# Task1.net
KiCad netlist of a schematic drawn in Altium Designer
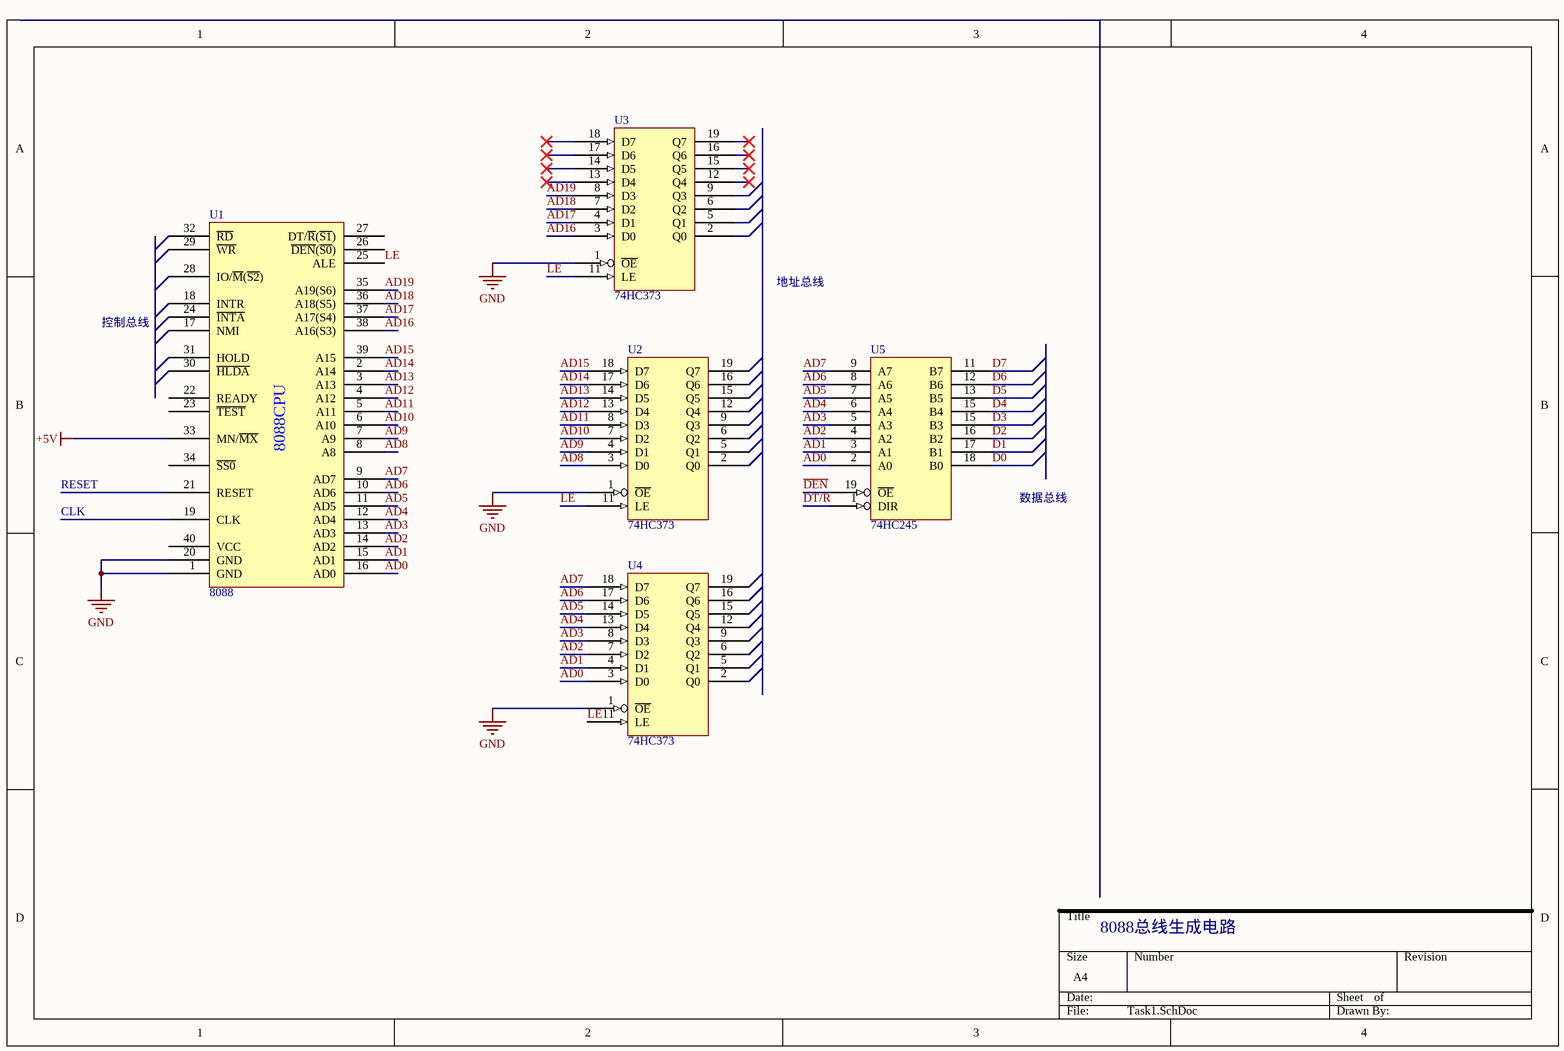
[diagram p0: Task1.SchDoc]

(export (version "E")
  (design (tool "Eeschema 10.0.6"))
  (components
    (comp (ref "U1") (value "8088") (libsource (lib "8088ThreeBuses") (part "8088")))
    (comp (ref "U2") (value "74HC373") (libsource (lib "8088ThreeBuses") (part "74HC373")))
    (comp (ref "U3") (value "74HC373") (libsource (lib "8088ThreeBuses") (part "74HC373")))
    (comp (ref "U4") (value "74HC373") (libsource (lib "8088ThreeBuses") (part "74HC373")))
    (comp (ref "U5") (value "74HC245") (libsource (lib "8088ThreeBuses") (part "74HC245")))
  )
  (nets
    (net (code "1") (name "+5V") (class "Default")
      (node (ref "U1") (pin "33") (pinfunction "MN/~{MX}_33") (pintype "passive"))
    )
    (net (code "2") (name "/AD0") (class "Default")
      (node (ref "U1") (pin "16") (pinfunction "AD0_16") (pintype "passive"))
      (node (ref "U4") (pin "3") (pinfunction "D0_3") (pintype "input"))
      (node (ref "U5") (pin "2") (pinfunction "A0_2") (pintype "passive"))
    )
    (net (code "3") (name "/AD1") (class "Default")
      (node (ref "U1") (pin "15") (pinfunction "AD1_15") (pintype "passive"))
      (node (ref "U4") (pin "4") (pinfunction "D1_4") (pintype "input"))
      (node (ref "U5") (pin "3") (pinfunction "A1_3") (pintype "passive"))
    )
    (net (code "4") (name "/AD2") (class "Default")
      (node (ref "U1") (pin "14") (pinfunction "AD2_14") (pintype "passive"))
      (node (ref "U4") (pin "7") (pinfunction "D2_7") (pintype "input"))
      (node (ref "U5") (pin "4") (pinfunction "A2_4") (pintype "passive"))
    )
    (net (code "5") (name "/AD3") (class "Default")
      (node (ref "U1") (pin "13") (pinfunction "AD3_13") (pintype "passive"))
      (node (ref "U4") (pin "8") (pinfunction "D3_8") (pintype "input"))
      (node (ref "U5") (pin "5") (pinfunction "A3_5") (pintype "passive"))
    )
    (net (code "6") (name "/AD4") (class "Default")
      (node (ref "U1") (pin "12") (pinfunction "AD4_12") (pintype "passive"))
      (node (ref "U4") (pin "13") (pinfunction "D4_13") (pintype "input"))
      (node (ref "U5") (pin "6") (pinfunction "A4_6") (pintype "passive"))
    )
    (net (code "7") (name "/AD5") (class "Default")
      (node (ref "U1") (pin "11") (pinfunction "AD5_11") (pintype "passive"))
      (node (ref "U4") (pin "14") (pinfunction "D5_14") (pintype "input"))
      (node (ref "U5") (pin "7") (pinfunction "A5_7") (pintype "passive"))
    )
    (net (code "8") (name "/AD6") (class "Default")
      (node (ref "U1") (pin "10") (pinfunction "AD6_10") (pintype "passive"))
      (node (ref "U4") (pin "17") (pinfunction "D6_17") (pintype "input"))
      (node (ref "U5") (pin "8") (pinfunction "A6_8") (pintype "passive"))
    )
    (net (code "9") (name "/AD7") (class "Default")
      (node (ref "U1") (pin "9") (pinfunction "AD7_9") (pintype "passive"))
      (node (ref "U4") (pin "18") (pinfunction "D7_18") (pintype "input"))
      (node (ref "U5") (pin "9") (pinfunction "A7_9") (pintype "passive"))
    )
    (net (code "10") (name "/AD8") (class "Default")
      (node (ref "U1") (pin "8") (pinfunction "A8_8") (pintype "passive"))
      (node (ref "U2") (pin "3") (pinfunction "D0_3") (pintype "input"))
    )
    (net (code "11") (name "/AD9") (class "Default")
      (node (ref "U1") (pin "7") (pinfunction "A9_7") (pintype "passive"))
      (node (ref "U2") (pin "4") (pinfunction "D1_4") (pintype "input"))
    )
    (net (code "12") (name "/AD10") (class "Default")
      (node (ref "U1") (pin "6") (pinfunction "A10_6") (pintype "passive"))
      (node (ref "U2") (pin "7") (pinfunction "D2_7") (pintype "input"))
    )
    (net (code "13") (name "/AD11") (class "Default")
      (node (ref "U1") (pin "5") (pinfunction "A11_5") (pintype "passive"))
      (node (ref "U2") (pin "8") (pinfunction "D3_8") (pintype "input"))
    )
    (net (code "14") (name "/AD12") (class "Default")
      (node (ref "U1") (pin "4") (pinfunction "A12_4") (pintype "passive"))
      (node (ref "U2") (pin "13") (pinfunction "D4_13") (pintype "input"))
    )
    (net (code "15") (name "/AD13") (class "Default")
      (node (ref "U1") (pin "3") (pinfunction "A13_3") (pintype "passive"))
      (node (ref "U2") (pin "14") (pinfunction "D5_14") (pintype "input"))
    )
    (net (code "16") (name "/AD14") (class "Default")
      (node (ref "U1") (pin "2") (pinfunction "A14_2") (pintype "passive"))
      (node (ref "U2") (pin "17") (pinfunction "D6_17") (pintype "input"))
    )
    (net (code "17") (name "/AD15") (class "Default")
      (node (ref "U1") (pin "39") (pinfunction "A15_39") (pintype "passive"))
      (node (ref "U2") (pin "18") (pinfunction "D7_18") (pintype "input"))
    )
    (net (code "18") (name "/AD16") (class "Default")
      (node (ref "U1") (pin "38") (pinfunction "A16(S3)_38") (pintype "passive"))
      (node (ref "U3") (pin "3") (pinfunction "D0_3") (pintype "input"))
    )
    (net (code "19") (name "/AD17") (class "Default")
      (node (ref "U1") (pin "37") (pinfunction "A17(S4)_37") (pintype "passive"))
      (node (ref "U3") (pin "4") (pinfunction "D1_4") (pintype "input"))
    )
    (net (code "20") (name "/AD18") (class "Default")
      (node (ref "U1") (pin "36") (pinfunction "A18(S5)_36") (pintype "passive"))
      (node (ref "U3") (pin "7") (pinfunction "D2_7") (pintype "input"))
    )
    (net (code "21") (name "/AD19") (class "Default")
      (node (ref "U1") (pin "35") (pinfunction "A19(S6)_35") (pintype "passive"))
      (node (ref "U3") (pin "8") (pinfunction "D3_8") (pintype "input"))
    )
    (net (code "22") (name "/D0") (class "Default")
      (node (ref "U5") (pin "18") (pinfunction "B0_18") (pintype "tri_state"))
    )
    (net (code "23") (name "/D1") (class "Default")
      (node (ref "U5") (pin "17") (pinfunction "B1_17") (pintype "tri_state"))
    )
    (net (code "24") (name "/D2") (class "Default")
      (node (ref "U5") (pin "16") (pinfunction "B2_16") (pintype "tri_state"))
    )
    (net (code "25") (name "/D3") (class "Default")
      (node (ref "U5") (pin "15") (pinfunction "B3_15") (pintype "tri_state"))
    )
    (net (code "26") (name "/D4") (class "Default")
      (node (ref "U5") (pin "15") (pinfunction "B4_15") (pintype "tri_state"))
    )
    (net (code "27") (name "/D5") (class "Default")
      (node (ref "U5") (pin "13") (pinfunction "B5_13") (pintype "tri_state"))
    )
    (net (code "28") (name "/D6") (class "Default")
      (node (ref "U5") (pin "12") (pinfunction "B6_12") (pintype "tri_state"))
    )
    (net (code "29") (name "/D7") (class "Default")
      (node (ref "U5") (pin "11") (pinfunction "B7_11") (pintype "tri_state"))
    )
    (net (code "30") (name "/DT{slash}~{R}") (class "Default")
      (node (ref "U5") (pin "1") (pinfunction "DIR_1") (pintype "input"))
    )
    (net (code "31") (name "/LE") (class "Default")
      (node (ref "U1") (pin "25") (pinfunction "ALE_25") (pintype "passive"))
      (node (ref "U2") (pin "11") (pinfunction "LE_11") (pintype "input"))
      (node (ref "U3") (pin "11") (pinfunction "LE_11") (pintype "input"))
      (node (ref "U4") (pin "11") (pinfunction "LE_11") (pintype "input"))
    )
    (net (code "32") (name "/~{DEN}") (class "Default")
      (node (ref "U5") (pin "19") (pinfunction "~{OE}_19") (pintype "input"))
    )
    (net (code "33") (name "GND") (class "Default")
      (node (ref "U1") (pin "1") (pinfunction "GND_1") (pintype "passive"))
      (node (ref "U1") (pin "20") (pinfunction "GND_20") (pintype "passive"))
      (node (ref "U2") (pin "1") (pinfunction "~{OE}_1") (pintype "input"))
      (node (ref "U3") (pin "1") (pinfunction "~{OE}_1") (pintype "input"))
      (node (ref "U4") (pin "1") (pinfunction "~{OE}_1") (pintype "input"))
    )
    (net (code "34") (name "unconnected-(U1-CLK-Pad19)") (class "Default")
      (node (ref "U1") (pin "19") (pinfunction "CLK_19") (pintype "passive"))
    )
    (net (code "35") (name "unconnected-(U1-DT{slash}~{R}(~{S1})-Pad27)") (class "Default")
      (node (ref "U1") (pin "27") (pinfunction "DT/~{R}(~{S1})_27") (pintype "passive"))
    )
    (net (code "36") (name "unconnected-(U1-HOLD-Pad31)") (class "Default")
      (node (ref "U1") (pin "31") (pinfunction "HOLD_31") (pintype "passive"))
    )
    (net (code "37") (name "unconnected-(U1-INTR-Pad18)") (class "Default")
      (node (ref "U1") (pin "18") (pinfunction "INTR_18") (pintype "passive"))
    )
    (net (code "38") (name "unconnected-(U1-IO{slash}~{M}(~{S2})-Pad28)") (class "Default")
      (node (ref "U1") (pin "28") (pinfunction "IO/~{M}(~{S2})_28") (pintype "passive"))
    )
    (net (code "39") (name "unconnected-(U1-NMI-Pad17)") (class "Default")
      (node (ref "U1") (pin "17") (pinfunction "NMI_17") (pintype "passive"))
    )
    (net (code "40") (name "unconnected-(U1-READY-Pad22)") (class "Default")
      (node (ref "U1") (pin "22") (pinfunction "READY_22") (pintype "passive"))
    )
    (net (code "41") (name "unconnected-(U1-RESET-Pad21)") (class "Default")
      (node (ref "U1") (pin "21") (pinfunction "RESET_21") (pintype "passive"))
    )
    (net (code "42") (name "unconnected-(U1-VCC-Pad40)") (class "Default")
      (node (ref "U1") (pin "40") (pinfunction "VCC_40") (pintype "passive"))
    )
    (net (code "43") (name "unconnected-(U1-~{DEN}(~{S0})-Pad26)") (class "Default")
      (node (ref "U1") (pin "26") (pinfunction "~{DEN}(~{S0})_26") (pintype "passive"))
    )
    (net (code "44") (name "unconnected-(U1-~{HLDA}-Pad30)") (class "Default")
      (node (ref "U1") (pin "30") (pinfunction "~{HLDA}_30") (pintype "passive"))
    )
    (net (code "45") (name "unconnected-(U1-~{INTA}-Pad24)") (class "Default")
      (node (ref "U1") (pin "24") (pinfunction "~{INTA}_24") (pintype "passive"))
    )
    (net (code "46") (name "unconnected-(U1-~{RD}-Pad32)") (class "Default")
      (node (ref "U1") (pin "32") (pinfunction "~{RD}_32") (pintype "passive"))
    )
    (net (code "47") (name "unconnected-(U1-~{SS0}-Pad34)") (class "Default")
      (node (ref "U1") (pin "34") (pinfunction "~{SS0}_34") (pintype "passive"))
    )
    (net (code "48") (name "unconnected-(U1-~{TEST}-Pad23)") (class "Default")
      (node (ref "U1") (pin "23") (pinfunction "~{TEST}_23") (pintype "passive"))
    )
    (net (code "49") (name "unconnected-(U1-~{WR}-Pad29)") (class "Default")
      (node (ref "U1") (pin "29") (pinfunction "~{WR}_29") (pintype "passive"))
    )
    (net (code "50") (name "unconnected-(U2-Q0-Pad2)") (class "Default")
      (node (ref "U2") (pin "2") (pinfunction "Q0_2") (pintype "tri_state"))
    )
    (net (code "51") (name "unconnected-(U2-Q1-Pad5)") (class "Default")
      (node (ref "U2") (pin "5") (pinfunction "Q1_5") (pintype "tri_state"))
    )
    (net (code "52") (name "unconnected-(U2-Q2-Pad6)") (class "Default")
      (node (ref "U2") (pin "6") (pinfunction "Q2_6") (pintype "tri_state"))
    )
    (net (code "53") (name "unconnected-(U2-Q3-Pad9)") (class "Default")
      (node (ref "U2") (pin "9") (pinfunction "Q3_9") (pintype "tri_state"))
    )
    (net (code "54") (name "unconnected-(U2-Q4-Pad12)") (class "Default")
      (node (ref "U2") (pin "12") (pinfunction "Q4_12") (pintype "tri_state"))
    )
    (net (code "55") (name "unconnected-(U2-Q5-Pad15)") (class "Default")
      (node (ref "U2") (pin "15") (pinfunction "Q5_15") (pintype "tri_state"))
    )
    (net (code "56") (name "unconnected-(U2-Q6-Pad16)") (class "Default")
      (node (ref "U2") (pin "16") (pinfunction "Q6_16") (pintype "tri_state"))
    )
    (net (code "57") (name "unconnected-(U2-Q7-Pad19)") (class "Default")
      (node (ref "U2") (pin "19") (pinfunction "Q7_19") (pintype "tri_state"))
    )
    (net (code "58") (name "unconnected-(U3-D4-Pad13)") (class "Default")
      (node (ref "U3") (pin "13") (pinfunction "D4_13") (pintype "input+no_connect"))
    )
    (net (code "59") (name "unconnected-(U3-D5-Pad14)") (class "Default")
      (node (ref "U3") (pin "14") (pinfunction "D5_14") (pintype "input+no_connect"))
    )
    (net (code "60") (name "unconnected-(U3-D6-Pad17)") (class "Default")
      (node (ref "U3") (pin "17") (pinfunction "D6_17") (pintype "input+no_connect"))
    )
    (net (code "61") (name "unconnected-(U3-D7-Pad18)") (class "Default")
      (node (ref "U3") (pin "18") (pinfunction "D7_18") (pintype "input+no_connect"))
    )
    (net (code "62") (name "unconnected-(U3-Q0-Pad2)") (class "Default")
      (node (ref "U3") (pin "2") (pinfunction "Q0_2") (pintype "tri_state"))
    )
    (net (code "63") (name "unconnected-(U3-Q1-Pad5)") (class "Default")
      (node (ref "U3") (pin "5") (pinfunction "Q1_5") (pintype "tri_state"))
    )
    (net (code "64") (name "unconnected-(U3-Q2-Pad6)") (class "Default")
      (node (ref "U3") (pin "6") (pinfunction "Q2_6") (pintype "tri_state"))
    )
    (net (code "65") (name "unconnected-(U3-Q3-Pad9)") (class "Default")
      (node (ref "U3") (pin "9") (pinfunction "Q3_9") (pintype "tri_state"))
    )
    (net (code "66") (name "unconnected-(U3-Q4-Pad12)") (class "Default")
      (node (ref "U3") (pin "12") (pinfunction "Q4_12") (pintype "tri_state+no_connect"))
    )
    (net (code "67") (name "unconnected-(U3-Q5-Pad15)") (class "Default")
      (node (ref "U3") (pin "15") (pinfunction "Q5_15") (pintype "tri_state+no_connect"))
    )
    (net (code "68") (name "unconnected-(U3-Q6-Pad16)") (class "Default")
      (node (ref "U3") (pin "16") (pinfunction "Q6_16") (pintype "tri_state+no_connect"))
    )
    (net (code "69") (name "unconnected-(U3-Q7-Pad19)") (class "Default")
      (node (ref "U3") (pin "19") (pinfunction "Q7_19") (pintype "tri_state+no_connect"))
    )
    (net (code "70") (name "unconnected-(U4-Q0-Pad2)") (class "Default")
      (node (ref "U4") (pin "2") (pinfunction "Q0_2") (pintype "tri_state"))
    )
    (net (code "71") (name "unconnected-(U4-Q1-Pad5)") (class "Default")
      (node (ref "U4") (pin "5") (pinfunction "Q1_5") (pintype "tri_state"))
    )
    (net (code "72") (name "unconnected-(U4-Q2-Pad6)") (class "Default")
      (node (ref "U4") (pin "6") (pinfunction "Q2_6") (pintype "tri_state"))
    )
    (net (code "73") (name "unconnected-(U4-Q3-Pad9)") (class "Default")
      (node (ref "U4") (pin "9") (pinfunction "Q3_9") (pintype "tri_state"))
    )
    (net (code "74") (name "unconnected-(U4-Q4-Pad12)") (class "Default")
      (node (ref "U4") (pin "12") (pinfunction "Q4_12") (pintype "tri_state"))
    )
    (net (code "75") (name "unconnected-(U4-Q5-Pad15)") (class "Default")
      (node (ref "U4") (pin "15") (pinfunction "Q5_15") (pintype "tri_state"))
    )
    (net (code "76") (name "unconnected-(U4-Q6-Pad16)") (class "Default")
      (node (ref "U4") (pin "16") (pinfunction "Q6_16") (pintype "tri_state"))
    )
    (net (code "77") (name "unconnected-(U4-Q7-Pad19)") (class "Default")
      (node (ref "U4") (pin "19") (pinfunction "Q7_19") (pintype "tri_state"))
    )
  )
)
